# 4mb.net
KiCad netlist of a schematic drawn in EAGLE
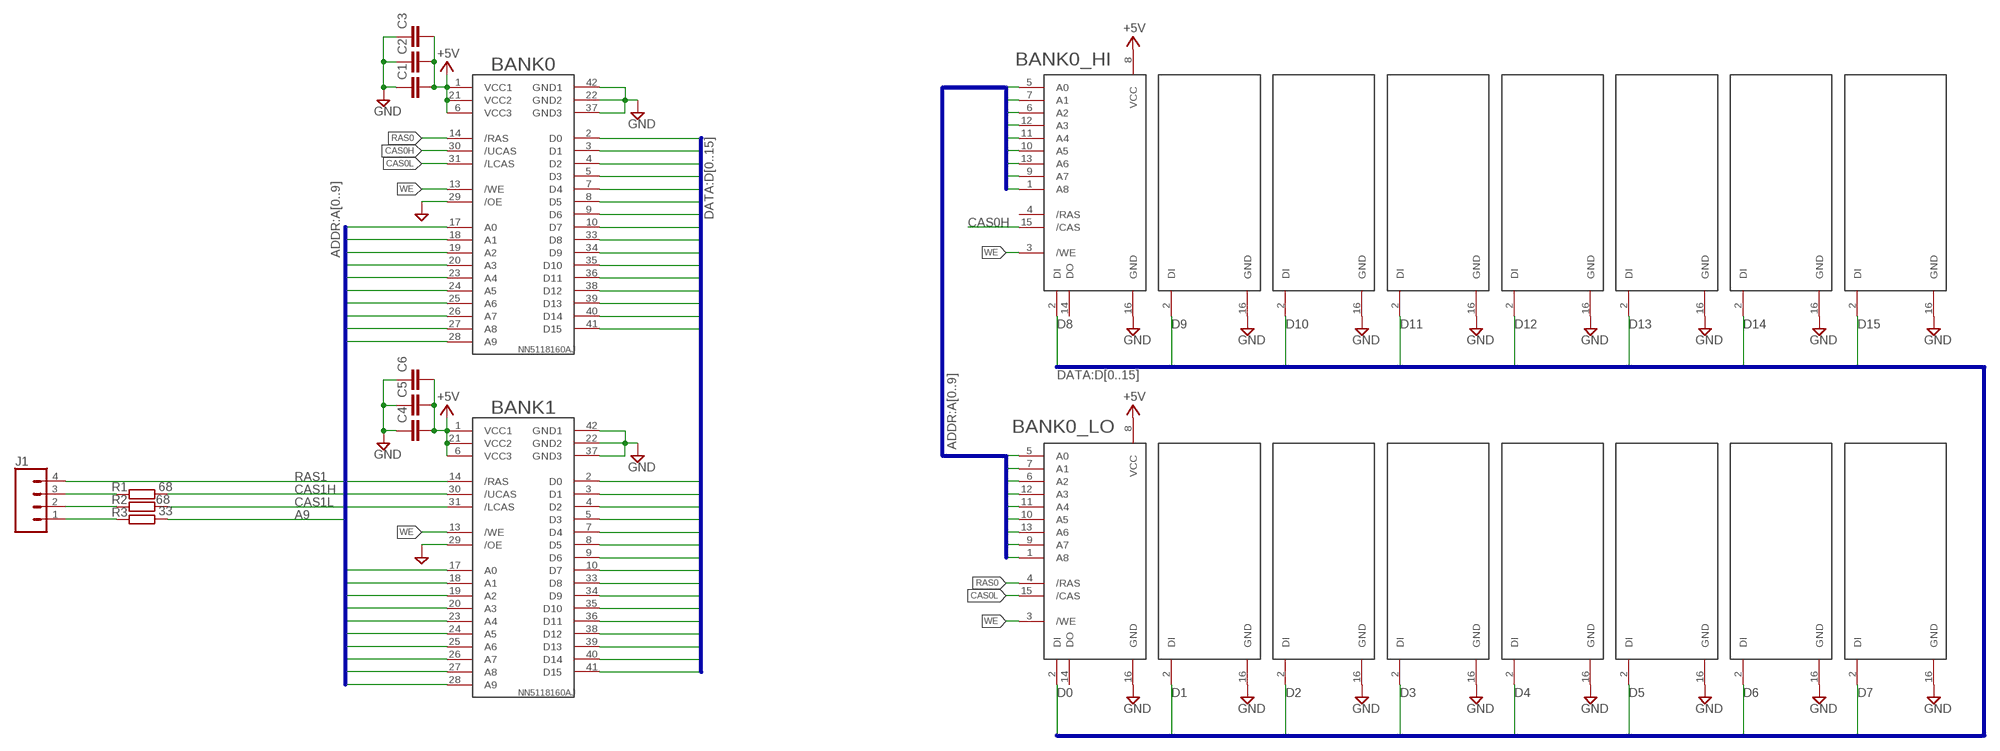
[diagram p0: schematic, sheet 1]

(export (version "E")
  (design (tool "Eeschema 10.0.6"))
  (components
    (comp (ref "C1")
      (value "C-EUC0805")
      (footprint "eagle-import:C0805")
      (libsource (lib "eagle-import") (part "C-EUC0805"))
    )
    (comp (ref "C2")
      (value "C-EUC0805")
      (footprint "eagle-import:C0805")
      (libsource (lib "eagle-import") (part "C-EUC0805"))
    )
    (comp (ref "C3")
      (value "C-EUC0805")
      (footprint "eagle-import:C0805")
      (libsource (lib "eagle-import") (part "C-EUC0805"))
    )
    (comp (ref "C4")
      (value "C-EUC0805")
      (footprint "eagle-import:C0805")
      (libsource (lib "eagle-import") (part "C-EUC0805"))
    )
    (comp (ref "C5")
      (value "C-EUC0805")
      (footprint "eagle-import:C0805")
      (libsource (lib "eagle-import") (part "C-EUC0805"))
    )
    (comp (ref "C6")
      (value "C-EUC0805")
      (footprint "eagle-import:C0805")
      (libsource (lib "eagle-import") (part "C-EUC0805"))
    )
    (comp (ref "J1")
      (value "CONN_04PTH")
      (footprint "eagle-import:1X04")
      (libsource (lib "eagle-import") (part "CONN_04PTH"))
    )
    (comp (ref "R1")
      (value "68")
      (footprint "eagle-import:R0805")
      (libsource (lib "eagle-import") (part "R-EU_R0805"))
    )
    (comp (ref "R2")
      (value "68")
      (footprint "eagle-import:R0805")
      (libsource (lib "eagle-import") (part "R-EU_R0805"))
    )
    (comp (ref "R3")
      (value "33")
      (footprint "eagle-import:R0805")
      (libsource (lib "eagle-import") (part "R-EU_R0805"))
    )
    (comp (ref "U$1")
      (value "NN5118160AJ")
      (footprint "eagle-import:SOJ127P1117X376-42")
      (libsource (lib "eagle-import") (part "NN5118160AJ"))
    )
    (comp (ref "U$2")
      (value "NN5118160AJ")
      (footprint "eagle-import:SOJ127P1117X376-42")
      (libsource (lib "eagle-import") (part "NN5118160AJ"))
    )
    (comp (ref "U$3")
      (value "ST_DRAM")
      (footprint "eagle-import:DIL16")
      (libsource (lib "eagle-import") (part "ST_DRAM"))
    )
    (comp (ref "U$4")
      (value "ST_DRAM_D")
      (footprint "eagle-import:ST_DRAM_SOCKET_MINIMAL")
      (libsource (lib "eagle-import") (part "ST_DRAM_D"))
    )
    (comp (ref "U$5")
      (value "ST_DRAM_D")
      (footprint "eagle-import:ST_DRAM_SOCKET_MINIMAL")
      (libsource (lib "eagle-import") (part "ST_DRAM_D"))
    )
    (comp (ref "U$6")
      (value "ST_DRAM_D")
      (footprint "eagle-import:ST_DRAM_SOCKET_MINIMAL")
      (libsource (lib "eagle-import") (part "ST_DRAM_D"))
    )
    (comp (ref "U$7")
      (value "ST_DRAM_D")
      (footprint "eagle-import:ST_DRAM_SOCKET_MINIMAL")
      (libsource (lib "eagle-import") (part "ST_DRAM_D"))
    )
    (comp (ref "U$8")
      (value "ST_DRAM_D")
      (footprint "eagle-import:ST_DRAM_SOCKET_MINIMAL")
      (libsource (lib "eagle-import") (part "ST_DRAM_D"))
    )
    (comp (ref "U$9")
      (value "ST_DRAM_D")
      (footprint "eagle-import:ST_DRAM_SOCKET_MINIMAL")
      (libsource (lib "eagle-import") (part "ST_DRAM_D"))
    )
    (comp (ref "U$10")
      (value "ST_DRAM_D")
      (footprint "eagle-import:ST_DRAM_SOCKET_MINIMAL")
      (libsource (lib "eagle-import") (part "ST_DRAM_D"))
    )
    (comp (ref "U$11")
      (value "ST_DRAM")
      (footprint "eagle-import:DIL16")
      (libsource (lib "eagle-import") (part "ST_DRAM"))
    )
    (comp (ref "U$12")
      (value "ST_DRAM_D")
      (footprint "eagle-import:ST_DRAM_SOCKET_MINIMAL")
      (libsource (lib "eagle-import") (part "ST_DRAM_D"))
    )
    (comp (ref "U$13")
      (value "ST_DRAM_D")
      (footprint "eagle-import:ST_DRAM_SOCKET_MINIMAL")
      (libsource (lib "eagle-import") (part "ST_DRAM_D"))
    )
    (comp (ref "U$14")
      (value "ST_DRAM_D")
      (footprint "eagle-import:ST_DRAM_SOCKET_MINIMAL")
      (libsource (lib "eagle-import") (part "ST_DRAM_D"))
    )
    (comp (ref "U$15")
      (value "ST_DRAM_D")
      (footprint "eagle-import:ST_DRAM_SOCKET_MINIMAL")
      (libsource (lib "eagle-import") (part "ST_DRAM_D"))
    )
    (comp (ref "U$16")
      (value "ST_DRAM_D")
      (footprint "eagle-import:ST_DRAM_SOCKET_MINIMAL")
      (libsource (lib "eagle-import") (part "ST_DRAM_D"))
    )
    (comp (ref "U$17")
      (value "ST_DRAM_D")
      (footprint "eagle-import:ST_DRAM_SOCKET_MINIMAL")
      (libsource (lib "eagle-import") (part "ST_DRAM_D"))
    )
    (comp (ref "U$18")
      (value "ST_DRAM_D")
      (footprint "eagle-import:ST_DRAM_SOCKET_MINIMAL")
      (libsource (lib "eagle-import") (part "ST_DRAM_D"))
    )
  )
  (nets
    (net (code "27") (name "+5V") (class "Default")
      (node (ref "C1") (pin "2") (pinfunction "2_2") (pintype "passive"))
      (node (ref "C2") (pin "2") (pinfunction "2_2") (pintype "passive"))
      (node (ref "C3") (pin "2") (pinfunction "2_2") (pintype "passive"))
      (node (ref "C4") (pin "2") (pinfunction "2_2") (pintype "passive"))
      (node (ref "C5") (pin "2") (pinfunction "2_2") (pintype "passive"))
      (node (ref "C6") (pin "2") (pinfunction "2_2") (pintype "passive"))
      (node (ref "U$1") (pin "1") (pinfunction "VCC1_1") (pintype "bidirectional"))
      (node (ref "U$1") (pin "21") (pinfunction "VCC2_21") (pintype "bidirectional"))
      (node (ref "U$1") (pin "6") (pinfunction "VCC3_6") (pintype "bidirectional"))
      (node (ref "U$11") (pin "8") (pinfunction "VCC_8") (pintype "bidirectional"))
      (node (ref "U$2") (pin "1") (pinfunction "VCC1_1") (pintype "bidirectional"))
      (node (ref "U$2") (pin "21") (pinfunction "VCC2_21") (pintype "bidirectional"))
      (node (ref "U$2") (pin "6") (pinfunction "VCC3_6") (pintype "bidirectional"))
      (node (ref "U$3") (pin "8") (pinfunction "VCC_8") (pintype "bidirectional"))
    )
    (net (code "28") (name "/A0") (class "Default")
      (node (ref "U$1") (pin "17") (pinfunction "A0_17") (pintype "bidirectional"))
      (node (ref "U$11") (pin "5") (pinfunction "A0_5") (pintype "bidirectional"))
      (node (ref "U$2") (pin "17") (pinfunction "A0_17") (pintype "bidirectional"))
      (node (ref "U$3") (pin "5") (pinfunction "A0_5") (pintype "bidirectional"))
    )
    (net (code "29") (name "/A1") (class "Default")
      (node (ref "U$1") (pin "18") (pinfunction "A1_18") (pintype "bidirectional"))
      (node (ref "U$11") (pin "7") (pinfunction "A1_7") (pintype "bidirectional"))
      (node (ref "U$2") (pin "18") (pinfunction "A1_18") (pintype "bidirectional"))
      (node (ref "U$3") (pin "7") (pinfunction "A1_7") (pintype "bidirectional"))
    )
    (net (code "30") (name "/A2") (class "Default")
      (node (ref "U$1") (pin "19") (pinfunction "A2_19") (pintype "bidirectional"))
      (node (ref "U$11") (pin "6") (pinfunction "A2_6") (pintype "bidirectional"))
      (node (ref "U$2") (pin "19") (pinfunction "A2_19") (pintype "bidirectional"))
      (node (ref "U$3") (pin "6") (pinfunction "A2_6") (pintype "bidirectional"))
    )
    (net (code "31") (name "/A3") (class "Default")
      (node (ref "U$1") (pin "20") (pinfunction "A3_20") (pintype "bidirectional"))
      (node (ref "U$11") (pin "12") (pinfunction "A3_12") (pintype "bidirectional"))
      (node (ref "U$2") (pin "20") (pinfunction "A3_20") (pintype "bidirectional"))
      (node (ref "U$3") (pin "12") (pinfunction "A3_12") (pintype "bidirectional"))
    )
    (net (code "32") (name "/A4") (class "Default")
      (node (ref "U$1") (pin "23") (pinfunction "A4_23") (pintype "bidirectional"))
      (node (ref "U$11") (pin "11") (pinfunction "A4_11") (pintype "bidirectional"))
      (node (ref "U$2") (pin "23") (pinfunction "A4_23") (pintype "bidirectional"))
      (node (ref "U$3") (pin "11") (pinfunction "A4_11") (pintype "bidirectional"))
    )
    (net (code "33") (name "/A5") (class "Default")
      (node (ref "U$1") (pin "24") (pinfunction "A5_24") (pintype "bidirectional"))
      (node (ref "U$11") (pin "10") (pinfunction "A5_10") (pintype "bidirectional"))
      (node (ref "U$2") (pin "24") (pinfunction "A5_24") (pintype "bidirectional"))
      (node (ref "U$3") (pin "10") (pinfunction "A5_10") (pintype "bidirectional"))
    )
    (net (code "34") (name "/A6") (class "Default")
      (node (ref "U$1") (pin "25") (pinfunction "A6_25") (pintype "bidirectional"))
      (node (ref "U$11") (pin "13") (pinfunction "A6_13") (pintype "bidirectional"))
      (node (ref "U$2") (pin "25") (pinfunction "A6_25") (pintype "bidirectional"))
      (node (ref "U$3") (pin "13") (pinfunction "A6_13") (pintype "bidirectional"))
    )
    (net (code "35") (name "/A7") (class "Default")
      (node (ref "U$1") (pin "26") (pinfunction "A7_26") (pintype "bidirectional"))
      (node (ref "U$11") (pin "9") (pinfunction "A7_9") (pintype "bidirectional"))
      (node (ref "U$2") (pin "26") (pinfunction "A7_26") (pintype "bidirectional"))
      (node (ref "U$3") (pin "9") (pinfunction "A7_9") (pintype "bidirectional"))
    )
    (net (code "36") (name "/A8") (class "Default")
      (node (ref "U$1") (pin "27") (pinfunction "A8_27") (pintype "bidirectional"))
      (node (ref "U$11") (pin "1") (pinfunction "A8_1") (pintype "bidirectional"))
      (node (ref "U$2") (pin "27") (pinfunction "A8_27") (pintype "bidirectional"))
      (node (ref "U$3") (pin "1") (pinfunction "A8_1") (pintype "bidirectional"))
    )
    (net (code "37") (name "/A9") (class "Default")
      (node (ref "R3") (pin "2") (pinfunction "2_2") (pintype "passive"))
      (node (ref "U$1") (pin "28") (pinfunction "A9_28") (pintype "bidirectional"))
      (node (ref "U$2") (pin "28") (pinfunction "A9_28") (pintype "bidirectional"))
    )
    (net (code "39") (name "/CAS1H") (class "Default")
      (node (ref "R1") (pin "2") (pinfunction "2_2") (pintype "passive"))
      (node (ref "U$2") (pin "30") (pinfunction "/UCAS_30") (pintype "bidirectional"))
    )
    (net (code "40") (name "/CAS1L") (class "Default")
      (node (ref "R2") (pin "2") (pinfunction "2_2") (pintype "passive"))
      (node (ref "U$2") (pin "31") (pinfunction "/LCAS_31") (pintype "bidirectional"))
    )
    (net (code "41") (name "/D1") (class "Default")
      (node (ref "U$1") (pin "3") (pinfunction "D1_3") (pintype "bidirectional"))
      (node (ref "U$12") (pin "2") (pinfunction "DI_2") (pintype "bidirectional"))
      (node (ref "U$2") (pin "3") (pinfunction "D1_3") (pintype "bidirectional"))
    )
    (net (code "42") (name "/D2") (class "Default")
      (node (ref "U$1") (pin "4") (pinfunction "D2_4") (pintype "bidirectional"))
      (node (ref "U$13") (pin "2") (pinfunction "DI_2") (pintype "bidirectional"))
      (node (ref "U$2") (pin "4") (pinfunction "D2_4") (pintype "bidirectional"))
    )
    (net (code "43") (name "/D3") (class "Default")
      (node (ref "U$1") (pin "5") (pinfunction "D3_5") (pintype "bidirectional"))
      (node (ref "U$14") (pin "2") (pinfunction "DI_2") (pintype "bidirectional"))
      (node (ref "U$2") (pin "5") (pinfunction "D3_5") (pintype "bidirectional"))
    )
    (net (code "44") (name "/D4") (class "Default")
      (node (ref "U$1") (pin "7") (pinfunction "D4_7") (pintype "bidirectional"))
      (node (ref "U$15") (pin "2") (pinfunction "DI_2") (pintype "bidirectional"))
      (node (ref "U$2") (pin "7") (pinfunction "D4_7") (pintype "bidirectional"))
    )
    (net (code "45") (name "/D5") (class "Default")
      (node (ref "U$1") (pin "8") (pinfunction "D5_8") (pintype "bidirectional"))
      (node (ref "U$16") (pin "2") (pinfunction "DI_2") (pintype "bidirectional"))
      (node (ref "U$2") (pin "8") (pinfunction "D5_8") (pintype "bidirectional"))
    )
    (net (code "46") (name "/D6") (class "Default")
      (node (ref "U$1") (pin "9") (pinfunction "D6_9") (pintype "bidirectional"))
      (node (ref "U$17") (pin "2") (pinfunction "DI_2") (pintype "bidirectional"))
      (node (ref "U$2") (pin "9") (pinfunction "D6_9") (pintype "bidirectional"))
    )
    (net (code "47") (name "/D7") (class "Default")
      (node (ref "U$1") (pin "10") (pinfunction "D7_10") (pintype "bidirectional"))
      (node (ref "U$18") (pin "2") (pinfunction "DI_2") (pintype "bidirectional"))
      (node (ref "U$2") (pin "10") (pinfunction "D7_10") (pintype "bidirectional"))
    )
    (net (code "48") (name "/D8") (class "Default")
      (node (ref "U$1") (pin "33") (pinfunction "D8_33") (pintype "bidirectional"))
      (node (ref "U$2") (pin "33") (pinfunction "D8_33") (pintype "bidirectional"))
      (node (ref "U$3") (pin "2") (pinfunction "DI_2") (pintype "bidirectional"))
    )
    (net (code "49") (name "/D9") (class "Default")
      (node (ref "U$1") (pin "34") (pinfunction "D9_34") (pintype "bidirectional"))
      (node (ref "U$2") (pin "34") (pinfunction "D9_34") (pintype "bidirectional"))
      (node (ref "U$4") (pin "2") (pinfunction "DI_2") (pintype "bidirectional"))
    )
    (net (code "50") (name "/D10") (class "Default")
      (node (ref "U$1") (pin "35") (pinfunction "D10_35") (pintype "bidirectional"))
      (node (ref "U$2") (pin "35") (pinfunction "D10_35") (pintype "bidirectional"))
      (node (ref "U$5") (pin "2") (pinfunction "DI_2") (pintype "bidirectional"))
    )
    (net (code "51") (name "/D11") (class "Default")
      (node (ref "U$1") (pin "36") (pinfunction "D11_36") (pintype "bidirectional"))
      (node (ref "U$2") (pin "36") (pinfunction "D11_36") (pintype "bidirectional"))
      (node (ref "U$6") (pin "2") (pinfunction "DI_2") (pintype "bidirectional"))
    )
    (net (code "52") (name "/D12") (class "Default")
      (node (ref "U$1") (pin "38") (pinfunction "D12_38") (pintype "bidirectional"))
      (node (ref "U$2") (pin "38") (pinfunction "D12_38") (pintype "bidirectional"))
      (node (ref "U$7") (pin "2") (pinfunction "DI_2") (pintype "bidirectional"))
    )
    (net (code "53") (name "/D13") (class "Default")
      (node (ref "U$1") (pin "39") (pinfunction "D13_39") (pintype "bidirectional"))
      (node (ref "U$2") (pin "39") (pinfunction "D13_39") (pintype "bidirectional"))
      (node (ref "U$8") (pin "2") (pinfunction "DI_2") (pintype "bidirectional"))
    )
    (net (code "54") (name "/D14") (class "Default")
      (node (ref "U$1") (pin "40") (pinfunction "D14_40") (pintype "bidirectional"))
      (node (ref "U$2") (pin "40") (pinfunction "D14_40") (pintype "bidirectional"))
      (node (ref "U$9") (pin "2") (pinfunction "DI_2") (pintype "bidirectional"))
    )
    (net (code "55") (name "/D15") (class "Default")
      (node (ref "U$1") (pin "41") (pinfunction "D15_41") (pintype "bidirectional"))
      (node (ref "U$10") (pin "2") (pinfunction "DI_2") (pintype "bidirectional"))
      (node (ref "U$2") (pin "41") (pinfunction "D15_41") (pintype "bidirectional"))
    )
    (net (code "56") (name "/DATA:D0") (class "Default")
      (node (ref "U$1") (pin "2") (pinfunction "D0_2") (pintype "bidirectional"))
      (node (ref "U$11") (pin "2") (pinfunction "DI_2") (pintype "bidirectional"))
      (node (ref "U$2") (pin "2") (pinfunction "D0_2") (pintype "bidirectional"))
    )
    (net (code "58") (name "/RAS1") (class "Default")
      (node (ref "J1") (pin "4") (pinfunction "4_4") (pintype "passive"))
      (node (ref "U$2") (pin "14") (pinfunction "/RAS_14") (pintype "bidirectional"))
    )
    (net (code "59") (name "CAS0H") (class "Default")
      (node (ref "U$1") (pin "30") (pinfunction "/UCAS_30") (pintype "bidirectional"))
      (node (ref "U$3") (pin "15") (pinfunction "/CAS_15") (pintype "bidirectional"))
    )
    (net (code "60") (name "CAS0L") (class "Default")
      (node (ref "U$1") (pin "31") (pinfunction "/LCAS_31") (pintype "bidirectional"))
      (node (ref "U$11") (pin "15") (pinfunction "/CAS_15") (pintype "bidirectional"))
    )
    (net (code "61") (name "GND") (class "Default")
      (node (ref "C1") (pin "1") (pinfunction "1_1") (pintype "passive"))
      (node (ref "C2") (pin "1") (pinfunction "1_1") (pintype "passive"))
      (node (ref "C3") (pin "1") (pinfunction "1_1") (pintype "passive"))
      (node (ref "C4") (pin "1") (pinfunction "1_1") (pintype "passive"))
      (node (ref "C5") (pin "1") (pinfunction "1_1") (pintype "passive"))
      (node (ref "C6") (pin "1") (pinfunction "1_1") (pintype "passive"))
      (node (ref "U$1") (pin "22") (pinfunction "GND2_22") (pintype "bidirectional"))
      (node (ref "U$1") (pin "29") (pinfunction "/OE_29") (pintype "bidirectional"))
      (node (ref "U$1") (pin "37") (pinfunction "GND3_37") (pintype "bidirectional"))
      (node (ref "U$1") (pin "42") (pinfunction "GND1_42") (pintype "bidirectional"))
      (node (ref "U$10") (pin "16") (pinfunction "GND_16") (pintype "bidirectional"))
      (node (ref "U$11") (pin "16") (pinfunction "GND_16") (pintype "bidirectional"))
      (node (ref "U$12") (pin "16") (pinfunction "GND_16") (pintype "bidirectional"))
      (node (ref "U$13") (pin "16") (pinfunction "GND_16") (pintype "bidirectional"))
      (node (ref "U$14") (pin "16") (pinfunction "GND_16") (pintype "bidirectional"))
      (node (ref "U$15") (pin "16") (pinfunction "GND_16") (pintype "bidirectional"))
      (node (ref "U$16") (pin "16") (pinfunction "GND_16") (pintype "bidirectional"))
      (node (ref "U$17") (pin "16") (pinfunction "GND_16") (pintype "bidirectional"))
      (node (ref "U$18") (pin "16") (pinfunction "GND_16") (pintype "bidirectional"))
      (node (ref "U$2") (pin "22") (pinfunction "GND2_22") (pintype "bidirectional"))
      (node (ref "U$2") (pin "29") (pinfunction "/OE_29") (pintype "bidirectional"))
      (node (ref "U$2") (pin "37") (pinfunction "GND3_37") (pintype "bidirectional"))
      (node (ref "U$2") (pin "42") (pinfunction "GND1_42") (pintype "bidirectional"))
      (node (ref "U$3") (pin "16") (pinfunction "GND_16") (pintype "bidirectional"))
      (node (ref "U$4") (pin "16") (pinfunction "GND_16") (pintype "bidirectional"))
      (node (ref "U$5") (pin "16") (pinfunction "GND_16") (pintype "bidirectional"))
      (node (ref "U$6") (pin "16") (pinfunction "GND_16") (pintype "bidirectional"))
      (node (ref "U$7") (pin "16") (pinfunction "GND_16") (pintype "bidirectional"))
      (node (ref "U$8") (pin "16") (pinfunction "GND_16") (pintype "bidirectional"))
      (node (ref "U$9") (pin "16") (pinfunction "GND_16") (pintype "bidirectional"))
    )
    (net (code "62") (name "Net-(J1-Pad1)") (class "Default")
      (node (ref "J1") (pin "1") (pinfunction "1_1") (pintype "passive"))
      (node (ref "R3") (pin "1") (pinfunction "1_1") (pintype "passive"))
    )
    (net (code "63") (name "Net-(J1-Pad2)") (class "Default")
      (node (ref "J1") (pin "2") (pinfunction "2_2") (pintype "passive"))
      (node (ref "R2") (pin "1") (pinfunction "1_1") (pintype "passive"))
    )
    (net (code "64") (name "Net-(J1-Pad3)") (class "Default")
      (node (ref "J1") (pin "3") (pinfunction "3_3") (pintype "passive"))
      (node (ref "R1") (pin "1") (pinfunction "1_1") (pintype "passive"))
    )
    (net (code "65") (name "RAS0") (class "Default")
      (node (ref "U$1") (pin "14") (pinfunction "/RAS_14") (pintype "bidirectional"))
      (node (ref "U$11") (pin "4") (pinfunction "/RAS_4") (pintype "bidirectional"))
    )
    (net (code "66") (name "WE") (class "Default")
      (node (ref "U$1") (pin "13") (pinfunction "/WE_13") (pintype "bidirectional"))
      (node (ref "U$11") (pin "3") (pinfunction "/WE_3") (pintype "bidirectional"))
      (node (ref "U$2") (pin "13") (pinfunction "/WE_13") (pintype "bidirectional"))
      (node (ref "U$3") (pin "3") (pinfunction "/WE_3") (pintype "bidirectional"))
    )
    (net (code "67") (name "unconnected-(U$3-DO-Pad14)") (class "Default")
      (node (ref "U$3") (pin "14") (pinfunction "DO_14") (pintype "bidirectional"))
    )
    (net (code "68") (name "unconnected-(U$3-{slash}RAS-Pad4)") (class "Default")
      (node (ref "U$3") (pin "4") (pinfunction "/RAS_4") (pintype "bidirectional"))
    )
    (net (code "69") (name "unconnected-(U$11-DO-Pad14)") (class "Default")
      (node (ref "U$11") (pin "14") (pinfunction "DO_14") (pintype "bidirectional"))
    )
  )
)
